# powersupply.net
KiCad netlist of a schematic drawn in Altium Designer
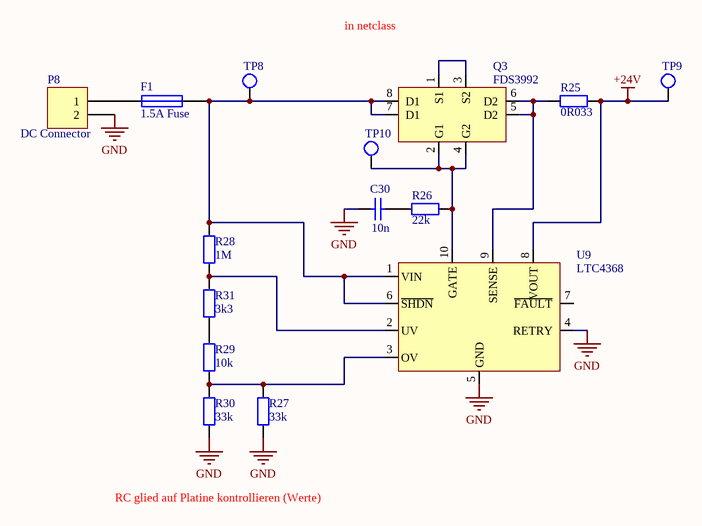
[diagram p0: powersupply.SchDoc]

(export (version "E")
  (design (tool "Eeschema 10.0.6"))
  (components
    (comp (ref "C30")
      (value "10n")
      (footprint "6-0805_M")
      (description "Capacitor")
      (fields (field (name "Comment") "Cap") (field (name "PUBLISHER") "Altium Limited"))
      (libsource (lib "Miscellaneous Devices") (part "Cap"))
    )
    (comp (ref "F1")
      (value "1.5A Fuse")
      (footprint "OMNI_BLOK_FUSE")
      (description "Fuse")
      (fields (field (name "PUBLISHER") "Altium Limited"))
      (libsource (lib "Miscellaneous Devices") (part "Fuse 1"))
    )
    (comp (ref "P8")
      (value "DC Connector")
      (footprint "HDR1X2")
      (description "Header, 2-Pin")
      (fields (field (name "PUBLISHER") "Altium Limited"))
      (libsource (lib "Miscellaneous Connectors") (part "Header 2"))
    )
    (comp (ref "Q3")
      (value "FDS3992")
      (footprint "SOIC-8")
      (description "FDS3992 Dual N-Channel MOSFET")
      (libsource (lib "clusterlib") (part "FDS3992"))
    )
    (comp (ref "R25")
      (value "0R033")
      (footprint "C1206")
      (description "Resistor")
      (fields (field (name "Comment") "Res2") (field (name "PUBLISHER") "Altium Limited"))
      (libsource (lib "") (part "Res2_1"))
    )
    (comp (ref "R26")
      (value "22k")
      (footprint "6-0805_M")
      (description "Resistor")
      (fields (field (name "Comment") "Res2") (field (name "PUBLISHER") "Altium Limited"))
      (libsource (lib "") (part "Res2_1"))
    )
    (comp (ref "R27")
      (value "33k")
      (footprint "6-0805_M")
      (description "Resistor")
      (fields (field (name "Comment") "Res2") (field (name "PUBLISHER") "Altium Limited"))
      (libsource (lib "Miscellaneous Devices") (part "Res2"))
    )
    (comp (ref "R28")
      (value "1M")
      (footprint "6-0805_M")
      (description "Resistor")
      (fields (field (name "Comment") "Res2") (field (name "PUBLISHER") "Altium Limited"))
      (libsource (lib "Miscellaneous Devices") (part "Res2"))
    )
    (comp (ref "R29")
      (value "10k")
      (footprint "6-0805_M")
      (description "Resistor")
      (fields (field (name "Comment") "Res2") (field (name "PUBLISHER") "Altium Limited"))
      (libsource (lib "Miscellaneous Devices") (part "Res2"))
    )
    (comp (ref "R30")
      (value "33k")
      (footprint "6-0805_M")
      (description "Resistor")
      (fields (field (name "Comment") "Res2") (field (name "PUBLISHER") "Altium Limited"))
      (libsource (lib "Miscellaneous Devices") (part "Res2"))
    )
    (comp (ref "R31")
      (value "3k3")
      (footprint "6-0805_M")
      (description "Resistor")
      (fields (field (name "Comment") "Res2") (field (name "PUBLISHER") "Altium Limited"))
      (libsource (lib "Miscellaneous Devices") (part "Res2"))
    )
    (comp (ref "TP8")
      (value "TestPoint")
      (footprint "MEASUREMENT_POINT")
      (description "Testpoint")
      (libsource (lib "clusterlib") (part "TestPoint"))
    )
    (comp (ref "TP9")
      (value "TestPoint")
      (footprint "MEASUREMENT_POINT")
      (description "Testpoint")
      (libsource (lib "clusterlib") (part "TestPoint"))
    )
    (comp (ref "TP10")
      (value "TestPoint")
      (footprint "MEASUREMENT_POINT")
      (description "Testpoint")
      (libsource (lib "clusterlib") (part "TestPoint"))
    )
    (comp (ref "U9")
      (value "LTC4368")
      (footprint "MSOP-10")
      (description "LTC4368 UV/OV/Reverse Protection IC")
      (libsource (lib "clusterlib") (part "LTC4368"))
    )
  )
  (nets
    (net (code "1") (name "+24V") (class "Default")
      (node (ref "R25") (pin "2") (pinfunction "2_2") (pintype "passive"))
      (node (ref "TP9") (pin "1") (pinfunction "1_1") (pintype "passive"))
      (node (ref "U9") (pin "8") (pinfunction "VOUT_8") (pintype "passive"))
    )
    (net (code "2") (name "GND") (class "Default")
      (node (ref "C30") (pin "1") (pinfunction "1_1") (pintype "passive"))
      (node (ref "P8") (pin "2") (pinfunction "2_2") (pintype "passive"))
      (node (ref "R27") (pin "1") (pinfunction "1_1") (pintype "passive"))
      (node (ref "R30") (pin "1") (pinfunction "1_1") (pintype "passive"))
      (node (ref "U9") (pin "4") (pinfunction "RETRY_4") (pintype "passive"))
      (node (ref "U9") (pin "5") (pinfunction "GND_5") (pintype "passive"))
    )
    (net (code "3") (name "Net-(C30-Pad2)") (class "Default")
      (node (ref "C30") (pin "2") (pinfunction "2_2") (pintype "passive"))
      (node (ref "R26") (pin "1") (pinfunction "1_1") (pintype "passive"))
    )
    (net (code "4") (name "Net-(F1-Pad1)") (class "Default")
      (node (ref "F1") (pin "1") (pinfunction "1_1") (pintype "passive"))
      (node (ref "P8") (pin "1") (pinfunction "1_1") (pintype "passive"))
    )
    (net (code "5") (name "Net-(Q3-G1)") (class "Default")
      (node (ref "Q3") (pin "2") (pinfunction "G1_2") (pintype "passive"))
      (node (ref "Q3") (pin "4") (pinfunction "G2_4") (pintype "passive"))
      (node (ref "R26") (pin "2") (pinfunction "2_2") (pintype "passive"))
      (node (ref "TP10") (pin "1") (pinfunction "1_1") (pintype "passive"))
      (node (ref "U9") (pin "10") (pinfunction "GATE_10") (pintype "passive"))
    )
    (net (code "6") (name "Net-(Q3-S1)") (class "Default")
      (node (ref "Q3") (pin "1") (pinfunction "S1_1") (pintype "passive"))
      (node (ref "Q3") (pin "3") (pinfunction "S2_3") (pintype "passive"))
    )
    (net (code "7") (name "Net-(R29-Pad2)") (class "Default")
      (node (ref "R29") (pin "2") (pinfunction "2_2") (pintype "passive"))
      (node (ref "R31") (pin "1") (pinfunction "1_1") (pintype "passive"))
    )
    (net (code "8") (name "Net-(U9-OV)") (class "Default")
      (node (ref "R27") (pin "2") (pinfunction "2_2") (pintype "passive"))
      (node (ref "R29") (pin "1") (pinfunction "1_1") (pintype "passive"))
      (node (ref "R30") (pin "2") (pinfunction "2_2") (pintype "passive"))
      (node (ref "U9") (pin "3") (pinfunction "OV_3") (pintype "passive"))
    )
    (net (code "9") (name "Net-(U9-SENSE)") (class "Default")
      (node (ref "Q3") (pin "5") (pinfunction "D2_5") (pintype "passive"))
      (node (ref "Q3") (pin "6") (pinfunction "D2_6") (pintype "passive"))
      (node (ref "R25") (pin "1") (pinfunction "1_1") (pintype "passive"))
      (node (ref "U9") (pin "9") (pinfunction "SENSE_9") (pintype "passive"))
    )
    (net (code "10") (name "Net-(U9-UV)") (class "Default")
      (node (ref "R28") (pin "1") (pinfunction "1_1") (pintype "passive"))
      (node (ref "R31") (pin "2") (pinfunction "2_2") (pintype "passive"))
      (node (ref "U9") (pin "2") (pinfunction "UV_2") (pintype "passive"))
    )
    (net (code "11") (name "Net-(U9-VIN)") (class "Default")
      (node (ref "F1") (pin "2") (pinfunction "2_2") (pintype "passive"))
      (node (ref "Q3") (pin "7") (pinfunction "D1_7") (pintype "passive"))
      (node (ref "Q3") (pin "8") (pinfunction "D1_8") (pintype "passive"))
      (node (ref "R28") (pin "2") (pinfunction "2_2") (pintype "passive"))
      (node (ref "TP8") (pin "1") (pinfunction "1_1") (pintype "passive"))
      (node (ref "U9") (pin "1") (pinfunction "VIN_1") (pintype "passive"))
      (node (ref "U9") (pin "6") (pinfunction "~{SHDN}_6") (pintype "passive"))
    )
    (net (code "12") (name "unconnected-(U9-~{FAULT}-Pad7)") (class "Default")
      (node (ref "U9") (pin "7") (pinfunction "~{FAULT}_7") (pintype "passive"))
    )
  )
)
